# PowerInput.net
KiCad netlist of a schematic drawn in Altium Designer
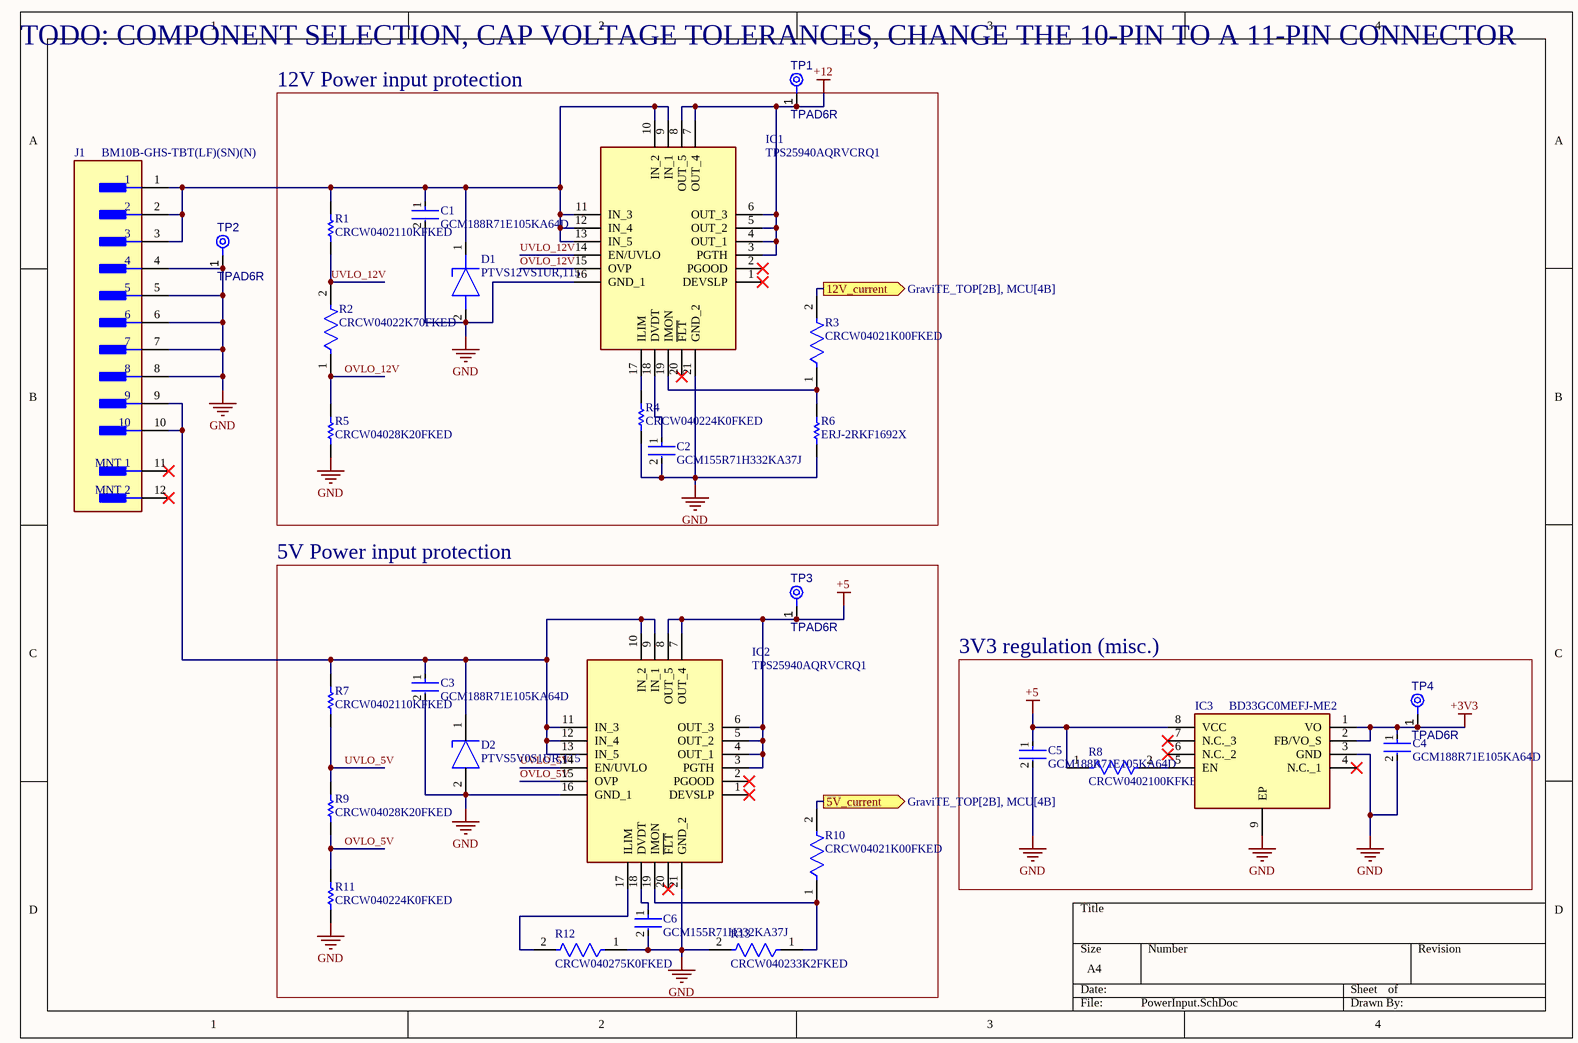
[diagram p0: PowerInput.SchDoc]

(export (version "E")
  (design (tool "Eeschema 10.0.6"))
  (components
    (comp (ref "C1")
      (value "GCM188R71E105KA64D")
      (footprint "FP-GCM188-0_1-MFG")
      (fields (field (name "TOLERANCE") "10%") (field (name "VOLTAGE") "25V"))
      (libsource (lib "Altium Content Vault") (part "02cd4be3c70576c341d710602a673aa"))
    )
    (comp (ref "C2")
      (value "GCM155R71H332KA37J")
      (footprint "FP-GCM155-0_05-MFG")
      (description "Ceramic Capacitor for Automotive 3.3nF ±10% 50VDC X7R 0402 Paper T/R")
      (fields (field (name "TOLERANCE") "10%"))
      (libsource (lib "Altium Content Vault") (part "02cd4be3c70576c341d710602a673aa"))
    )
    (comp (ref "C3")
      (value "GCM188R71E105KA64D")
      (footprint "FP-GCM188-0_1-MFG")
      (fields (field (name "TOLERANCE") "10%") (field (name "VOLTAGE") "25V"))
      (libsource (lib "Altium Content Vault") (part "02cd4be3c70576c341d710602a673aa"))
    )
    (comp (ref "C4")
      (value "GCM188R71E105KA64D")
      (footprint "FP-GCM188-0_1-MFG")
      (fields (field (name "TOLERANCE") "10%") (field (name "VOLTAGE") "25V"))
      (libsource (lib "Altium Content Vault") (part "02cd4be3c70576c341d710602a673aa"))
    )
    (comp (ref "C5")
      (value "GCM188R71E105KA64D")
      (footprint "FP-GCM188-0_1-MFG")
      (fields (field (name "TOLERANCE") "10%") (field (name "VOLTAGE") "25V"))
      (libsource (lib "Altium Content Vault") (part "02cd4be3c70576c341d710602a673aa"))
    )
    (comp (ref "C6")
      (value "GCM155R71H332KA37J")
      (footprint "FP-GCM155-0_05-MFG")
      (description "Ceramic Capacitor for Automotive 3.3nF ±10% 50VDC X7R 0402 Paper T/R")
      (fields (field (name "TOLERANCE") "10%"))
      (libsource (lib "Altium Content Vault") (part "02cd4be3c70576c341d710602a673aa"))
    )
    (comp (ref "D1")
      (value "PTVS12VS1UR,115")
      (footprint "SamacSys:SOD123W")
      (description "Diode ESD (Uni-directional)")
      (fields (field (name "MOUSER PART NUMBER") "771-PTVS12VS1UR115"))
      (libsource (lib "SamacSys") (part "PTVS12VS1UR,115"))
    )
    (comp (ref "D2")
      (value "PTVS5V0S1UR,115")
      (footprint "FP-SOD123W-MFG")
      (description "TVS DIODE 5VWM 9.2VC CFP3")
      (libsource (lib "Altium Content Vault") (part "e3b56fdaa181489d10e0c7edbf6f746"))
    )
    (comp (ref "IC1")
      (value "TPS25940AQRVCRQ1")
      (footprint "QFN50P300X400X80-21N")
      (description "Integrated Circuit")
      (fields (field (name "MOUSER PART NUMBER") "595-TPS25940AQRVCRQ1"))
      (libsource (lib "Cells_in_Space") (part "TPS25940AQRVCRQ1"))
    )
    (comp (ref "IC2")
      (value "TPS25940AQRVCRQ1")
      (footprint "QFN50P300X400X80-21N")
      (description "Integrated Circuit")
      (fields (field (name "MOUSER PART NUMBER") "595-TPS25940AQRVCRQ1"))
      (libsource (lib "Cells_in_Space") (part "TPS25940AQRVCRQ1"))
    )
    (comp (ref "IC3")
      (value "BD33GC0MEFJ-ME2")
      (footprint "SamacSys:SOIC127P600X100-9N")
      (description "Integrated Circuit")
      (fields (field (name "MOUSER PART NUMBER") "755-BD33GC0MEFJ-ME2"))
      (libsource (lib "SamacSys") (part "BD33GC0MEFJ-ME2"))
    )
    (comp (ref "J1")
      (value "BM10B-GHS-TBT(LF)(SN)(N)")
      (footprint "FP-BM10B-GHS-TBT_LF_SN-MFG")
      (description "CONN HEADER SMD 10POS 1.25MM")
      (libsource (lib "Altium Content Vault") (part "75b8bc8596cc75ee3b2e8049366f7d6"))
    )
    (comp (ref "R1")
      (value "CRCW0402110KFKED")
      (footprint "RESC1005X40X25NL05T05")
      (fields (field (name "MANUFACTURER") "Vishay Dale"))
      (libsource (lib "Altium Content Vault") (part "RES"))
    )
    (comp (ref "R2")
      (value "CRCW04022K70FKED")
      (footprint "FP-CRCW0402-e3-IPC_A")
      (description "RES Thick Film, 2.7kΩ, 1%, 0.063W, 100ppm/°C, 0402")
      (fields (field (name "TOLERANCE") "1%"))
      (libsource (lib "Altium Content Vault") (part "1029c3af85768c4190bb7ad29bc67b5"))
    )
    (comp (ref "R3")
      (value "CRCW04021K00FKED")
      (footprint "FP-CRCW0402-e3-MFG")
      (description "RES Thick Film, 1kΩ, 1%, 0.063W, 100ppm/°C, 0402")
      (fields (field (name "TOLERANCE") "1%"))
      (libsource (lib "Altium Content Vault") (part "1029c3af85768c4190bb7ad29bc67b5"))
    )
    (comp (ref "R4")
      (value "CRCW040224K0FKED")
      (footprint "RESC1005X40X25ML05T05")
      (fields (field (name "MANUFACTURER") "Vishay Dale"))
      (libsource (lib "Altium Content Vault") (part "RES"))
    )
    (comp (ref "R5")
      (value "CRCW04028K20FKED")
      (footprint "RESC1005X40X25ML05T05")
      (fields (field (name "MANUFACTURER") "Vishay Dale"))
      (libsource (lib "Altium Content Vault") (part "RES"))
    )
    (comp (ref "R6")
      (value "ERJ-2RKF1692X")
      (footprint "RESC1005X40X25ML05T05")
      (fields (field (name "MANUFACTURER") "Panasonic"))
      (libsource (lib "Altium Content Vault") (part "RES"))
    )
    (comp (ref "R7")
      (value "CRCW0402110KFKED")
      (footprint "RESC1005X40X25NL05T05")
      (fields (field (name "MANUFACTURER") "Vishay Dale"))
      (libsource (lib "Altium Content Vault") (part "RES"))
    )
    (comp (ref "R8")
      (value "CRCW0402100KFKED")
      (footprint "FP-CRCW0402-e3-IPC_C")
      (description "RES Thick Film, 100kΩ, 1%, 0.063W, 100ppm/°C, 0402")
      (fields (field (name "TOLERANCE") "1%"))
      (libsource (lib "Altium Content Vault") (part "1029c3af85768c4190bb7ad29bc67b5"))
    )
    (comp (ref "R9")
      (value "CRCW04028K20FKED")
      (footprint "RESC1005X40X25ML05T05")
      (fields (field (name "MANUFACTURER") "Vishay Dale"))
      (libsource (lib "Altium Content Vault") (part "RES"))
    )
    (comp (ref "R10")
      (value "CRCW04021K00FKED")
      (footprint "FP-CRCW0402-e3-MFG")
      (description "RES Thick Film, 1kΩ, 1%, 0.063W, 100ppm/°C, 0402")
      (fields (field (name "TOLERANCE") "1%"))
      (libsource (lib "Altium Content Vault") (part "1029c3af85768c4190bb7ad29bc67b5"))
    )
    (comp (ref "R11")
      (value "CRCW040224K0FKED")
      (footprint "RESC1005X40X25ML05T05")
      (fields (field (name "MANUFACTURER") "Vishay Dale"))
      (libsource (lib "Altium Content Vault") (part "RES"))
    )
    (comp (ref "R12")
      (value "CRCW040275K0FKED")
      (footprint "FP-CRCW0402-e3-IPC_A")
      (description "RES Thick Film, 75kΩ, 1%, 0.063W, 100ppm/°C, 0402")
      (fields (field (name "TOLERANCE") "1%"))
      (libsource (lib "Altium Content Vault") (part "1029c3af85768c4190bb7ad29bc67b5"))
    )
    (comp (ref "R13")
      (value "CRCW040233K2FKED")
      (footprint "Vishay_CRCW0402-e3_MFG")
      (fields (field (name "TOLERANCE") "1%"))
      (libsource (lib "Altium Content Vault") (part "CRCW040233K2FKED"))
    )
    (comp (ref "TP1")
      (value "TPAD6R")
      (footprint "TP06R")
      (description "0.6mm round")
      (libsource (lib "Piotr Słonka - priv") (part "CMP-001-0001-4"))
    )
    (comp (ref "TP2")
      (value "TPAD6R")
      (footprint "TP06R")
      (description "0.6mm round")
      (libsource (lib "Piotr Słonka - priv") (part "CMP-001-0001-4"))
    )
    (comp (ref "TP3")
      (value "TPAD6R")
      (footprint "TP06R")
      (description "0.6mm round")
      (libsource (lib "Piotr Słonka - priv") (part "CMP-001-0001-4"))
    )
    (comp (ref "TP4")
      (value "TPAD6R")
      (footprint "TP06R")
      (description "0.6mm round")
      (libsource (lib "Piotr Słonka - priv") (part "CMP-001-0001-4"))
    )
  )
  (nets
    (net (code "1") (name "+3V3") (class "Default")
      (node (ref "C4") (pin "1") (pinfunction "1_1") (pintype "passive"))
      (node (ref "IC3") (pin "1") (pinfunction "VO_1") (pintype "passive"))
      (node (ref "IC3") (pin "2") (pinfunction "FB/VO_S_2") (pintype "passive"))
      (node (ref "TP4") (pin "1") (pinfunction "TP_1") (pintype "passive"))
    )
    (net (code "2") (name "+5") (class "Default")
      (node (ref "C5") (pin "1") (pinfunction "1_1") (pintype "passive"))
      (node (ref "IC2") (pin "3") (pinfunction "PGTH_3") (pintype "passive"))
      (node (ref "IC2") (pin "4") (pinfunction "OUT_1_4") (pintype "passive"))
      (node (ref "IC2") (pin "5") (pinfunction "OUT_2_5") (pintype "passive"))
      (node (ref "IC2") (pin "6") (pinfunction "OUT_3_6") (pintype "passive"))
      (node (ref "IC2") (pin "7") (pinfunction "OUT_4_7") (pintype "passive"))
      (node (ref "IC2") (pin "8") (pinfunction "OUT_5_8") (pintype "passive"))
      (node (ref "IC3") (pin "8") (pinfunction "VCC_8") (pintype "passive"))
      (node (ref "R8") (pin "1") (pinfunction "1_1") (pintype "passive"))
      (node (ref "TP3") (pin "1") (pinfunction "TP_1") (pintype "passive"))
    )
    (net (code "3") (name "+12") (class "Default")
      (node (ref "IC1") (pin "3") (pinfunction "PGTH_3") (pintype "passive"))
      (node (ref "IC1") (pin "4") (pinfunction "OUT_1_4") (pintype "passive"))
      (node (ref "IC1") (pin "5") (pinfunction "OUT_2_5") (pintype "passive"))
      (node (ref "IC1") (pin "6") (pinfunction "OUT_3_6") (pintype "passive"))
      (node (ref "IC1") (pin "7") (pinfunction "OUT_4_7") (pintype "passive"))
      (node (ref "IC1") (pin "8") (pinfunction "OUT_5_8") (pintype "passive"))
      (node (ref "TP1") (pin "1") (pinfunction "TP_1") (pintype "passive"))
    )
    (net (code "4") (name "/5V_current") (class "Default")
      (node (ref "R10") (pin "2") (pinfunction "2_2") (pintype "passive"))
    )
    (net (code "5") (name "/12V_current") (class "Default")
      (node (ref "R3") (pin "2") (pinfunction "2_2") (pintype "passive"))
    )
    (net (code "6") (name "/OVLO_5V") (class "Default")
      (node (ref "IC2") (pin "15") (pinfunction "OVP_15") (pintype "passive"))
      (node (ref "R11") (pin "2") (pinfunction "2_2") (pintype "passive"))
      (node (ref "R9") (pin "1") (pinfunction "1_1") (pintype "passive"))
    )
    (net (code "7") (name "/OVLO_12V") (class "Default")
      (node (ref "IC1") (pin "15") (pinfunction "OVP_15") (pintype "passive"))
      (node (ref "R2") (pin "1") (pinfunction "1_1") (pintype "passive"))
      (node (ref "R5") (pin "2") (pinfunction "2_2") (pintype "passive"))
    )
    (net (code "8") (name "/UVLO_5V") (class "Default")
      (node (ref "IC2") (pin "14") (pinfunction "EN/UVLO_14") (pintype "passive"))
      (node (ref "R7") (pin "1") (pinfunction "1_1") (pintype "passive"))
      (node (ref "R9") (pin "2") (pinfunction "2_2") (pintype "passive"))
    )
    (net (code "9") (name "/UVLO_12V") (class "Default")
      (node (ref "IC1") (pin "14") (pinfunction "EN/UVLO_14") (pintype "passive"))
      (node (ref "R1") (pin "1") (pinfunction "1_1") (pintype "passive"))
      (node (ref "R2") (pin "2") (pinfunction "2_2") (pintype "passive"))
    )
    (net (code "10") (name "GND") (class "Default")
      (node (ref "C1") (pin "2") (pinfunction "2_2") (pintype "passive"))
      (node (ref "C2") (pin "2") (pinfunction "2_2") (pintype "passive"))
      (node (ref "C3") (pin "2") (pinfunction "2_2") (pintype "passive"))
      (node (ref "C4") (pin "2") (pinfunction "2_2") (pintype "passive"))
      (node (ref "C5") (pin "2") (pinfunction "2_2") (pintype "passive"))
      (node (ref "C6") (pin "2") (pinfunction "2_2") (pintype "passive"))
      (node (ref "D1") (pin "2") (pinfunction "A_2") (pintype "passive"))
      (node (ref "D2") (pin "2") (pinfunction "A_2") (pintype "passive"))
      (node (ref "IC1") (pin "16") (pinfunction "GND_1_16") (pintype "passive"))
      (node (ref "IC1") (pin "21") (pinfunction "GND_2_21") (pintype "passive"))
      (node (ref "IC2") (pin "16") (pinfunction "GND_1_16") (pintype "passive"))
      (node (ref "IC2") (pin "21") (pinfunction "GND_2_21") (pintype "passive"))
      (node (ref "IC3") (pin "3") (pinfunction "GND_3") (pintype "passive"))
      (node (ref "IC3") (pin "9") (pinfunction "EP_9") (pintype "passive"))
      (node (ref "J1") (pin "4") (pinfunction "4_4") (pintype "passive"))
      (node (ref "J1") (pin "5") (pinfunction "5_5") (pintype "passive"))
      (node (ref "J1") (pin "6") (pinfunction "6_6") (pintype "passive"))
      (node (ref "J1") (pin "7") (pinfunction "7_7") (pintype "passive"))
      (node (ref "J1") (pin "8") (pinfunction "8_8") (pintype "passive"))
      (node (ref "R11") (pin "1") (pinfunction "1_1") (pintype "passive"))
      (node (ref "R12") (pin "1") (pinfunction "1_1") (pintype "passive"))
      (node (ref "R13") (pin "2") (pinfunction "2_2") (pintype "passive"))
      (node (ref "R4") (pin "1") (pinfunction "1_1") (pintype "passive"))
      (node (ref "R5") (pin "1") (pinfunction "1_1") (pintype "passive"))
      (node (ref "R6") (pin "1") (pinfunction "1_1") (pintype "passive"))
      (node (ref "TP2") (pin "1") (pinfunction "TP_1") (pintype "passive"))
    )
    (net (code "11") (name "Net-(D1-K)") (class "Default")
      (node (ref "C1") (pin "1") (pinfunction "1_1") (pintype "passive"))
      (node (ref "D1") (pin "1") (pinfunction "K_1") (pintype "passive"))
      (node (ref "IC1") (pin "10") (pinfunction "IN_2_10") (pintype "passive"))
      (node (ref "IC1") (pin "11") (pinfunction "IN_3_11") (pintype "passive"))
      (node (ref "IC1") (pin "12") (pinfunction "IN_4_12") (pintype "passive"))
      (node (ref "IC1") (pin "13") (pinfunction "IN_5_13") (pintype "passive"))
      (node (ref "IC1") (pin "9") (pinfunction "IN_1_9") (pintype "passive"))
      (node (ref "J1") (pin "1") (pinfunction "1_1") (pintype "passive"))
      (node (ref "J1") (pin "2") (pinfunction "2_2") (pintype "passive"))
      (node (ref "J1") (pin "3") (pinfunction "3_3") (pintype "passive"))
      (node (ref "R1") (pin "2") (pinfunction "2_2") (pintype "passive"))
    )
    (net (code "12") (name "Net-(D2-C)") (class "Default")
      (node (ref "C3") (pin "1") (pinfunction "1_1") (pintype "passive"))
      (node (ref "D2") (pin "1") (pinfunction "C_1") (pintype "passive"))
      (node (ref "IC2") (pin "10") (pinfunction "IN_2_10") (pintype "passive"))
      (node (ref "IC2") (pin "11") (pinfunction "IN_3_11") (pintype "passive"))
      (node (ref "IC2") (pin "12") (pinfunction "IN_4_12") (pintype "passive"))
      (node (ref "IC2") (pin "13") (pinfunction "IN_5_13") (pintype "passive"))
      (node (ref "IC2") (pin "9") (pinfunction "IN_1_9") (pintype "passive"))
      (node (ref "J1") (pin "10") (pinfunction "10_10") (pintype "passive"))
      (node (ref "J1") (pin "9") (pinfunction "9_9") (pintype "passive"))
      (node (ref "R7") (pin "2") (pinfunction "2_2") (pintype "passive"))
    )
    (net (code "13") (name "Net-(IC1-DVDT)") (class "Default")
      (node (ref "C2") (pin "1") (pinfunction "1_1") (pintype "passive"))
      (node (ref "IC1") (pin "18") (pinfunction "DVDT_18") (pintype "passive"))
    )
    (net (code "14") (name "Net-(IC1-ILIM)") (class "Default")
      (node (ref "IC1") (pin "17") (pinfunction "ILIM_17") (pintype "passive"))
      (node (ref "R4") (pin "2") (pinfunction "2_2") (pintype "passive"))
    )
    (net (code "15") (name "Net-(IC1-IMON)") (class "Default")
      (node (ref "IC1") (pin "19") (pinfunction "IMON_19") (pintype "passive"))
      (node (ref "R3") (pin "1") (pinfunction "1_1") (pintype "passive"))
      (node (ref "R6") (pin "2") (pinfunction "2_2") (pintype "passive"))
    )
    (net (code "16") (name "Net-(IC2-DVDT)") (class "Default")
      (node (ref "C6") (pin "1") (pinfunction "1_1") (pintype "passive"))
      (node (ref "IC2") (pin "18") (pinfunction "DVDT_18") (pintype "passive"))
    )
    (net (code "17") (name "Net-(IC2-ILIM)") (class "Default")
      (node (ref "IC2") (pin "17") (pinfunction "ILIM_17") (pintype "passive"))
      (node (ref "R12") (pin "2") (pinfunction "2_2") (pintype "passive"))
    )
    (net (code "18") (name "Net-(IC2-IMON)") (class "Default")
      (node (ref "IC2") (pin "19") (pinfunction "IMON_19") (pintype "passive"))
      (node (ref "R10") (pin "1") (pinfunction "1_1") (pintype "passive"))
      (node (ref "R13") (pin "1") (pinfunction "1_1") (pintype "passive"))
    )
    (net (code "19") (name "Net-(IC3-EN)") (class "Default")
      (node (ref "IC3") (pin "5") (pinfunction "EN_5") (pintype "passive"))
      (node (ref "R8") (pin "2") (pinfunction "2_2") (pintype "passive"))
    )
    (net (code "20") (name "unconnected-(IC1-DEVSLP-Pad1)") (class "Default")
      (node (ref "IC1") (pin "1") (pinfunction "DEVSLP_1") (pintype "passive+no_connect"))
    )
    (net (code "21") (name "unconnected-(IC1-PGOOD-Pad2)") (class "Default")
      (node (ref "IC1") (pin "2") (pinfunction "PGOOD_2") (pintype "passive+no_connect"))
    )
    (net (code "22") (name "unconnected-(IC1-~{FLT}-Pad20)") (class "Default")
      (node (ref "IC1") (pin "20") (pinfunction "~{FLT}_20") (pintype "passive+no_connect"))
    )
    (net (code "23") (name "unconnected-(IC2-DEVSLP-Pad1)") (class "Default")
      (node (ref "IC2") (pin "1") (pinfunction "DEVSLP_1") (pintype "passive+no_connect"))
    )
    (net (code "24") (name "unconnected-(IC2-PGOOD-Pad2)") (class "Default")
      (node (ref "IC2") (pin "2") (pinfunction "PGOOD_2") (pintype "passive+no_connect"))
    )
    (net (code "25") (name "unconnected-(IC2-~{FLT}-Pad20)") (class "Default")
      (node (ref "IC2") (pin "20") (pinfunction "~{FLT}_20") (pintype "passive+no_connect"))
    )
    (net (code "26") (name "unconnected-(IC3-N.C._1-Pad4)") (class "Default")
      (node (ref "IC3") (pin "4") (pinfunction "N.C._1_4") (pintype "passive+no_connect"))
    )
    (net (code "27") (name "unconnected-(IC3-N.C._2-Pad6)") (class "Default")
      (node (ref "IC3") (pin "6") (pinfunction "N.C._2_6") (pintype "passive+no_connect"))
    )
    (net (code "28") (name "unconnected-(IC3-N.C._3-Pad7)") (class "Default")
      (node (ref "IC3") (pin "7") (pinfunction "N.C._3_7") (pintype "passive+no_connect"))
    )
    (net (code "29") (name "unconnected-(J1-MNT_1-Pad11)") (class "Default")
      (node (ref "J1") (pin "11") (pinfunction "MNT_1_11") (pintype "passive+no_connect"))
    )
    (net (code "30") (name "unconnected-(J1-MNT_2-Pad12)") (class "Default")
      (node (ref "J1") (pin "12") (pinfunction "MNT_2_12") (pintype "passive+no_connect"))
    )
  )
)
